# precharge.net
KiCad netlist of a schematic drawn in EAGLE
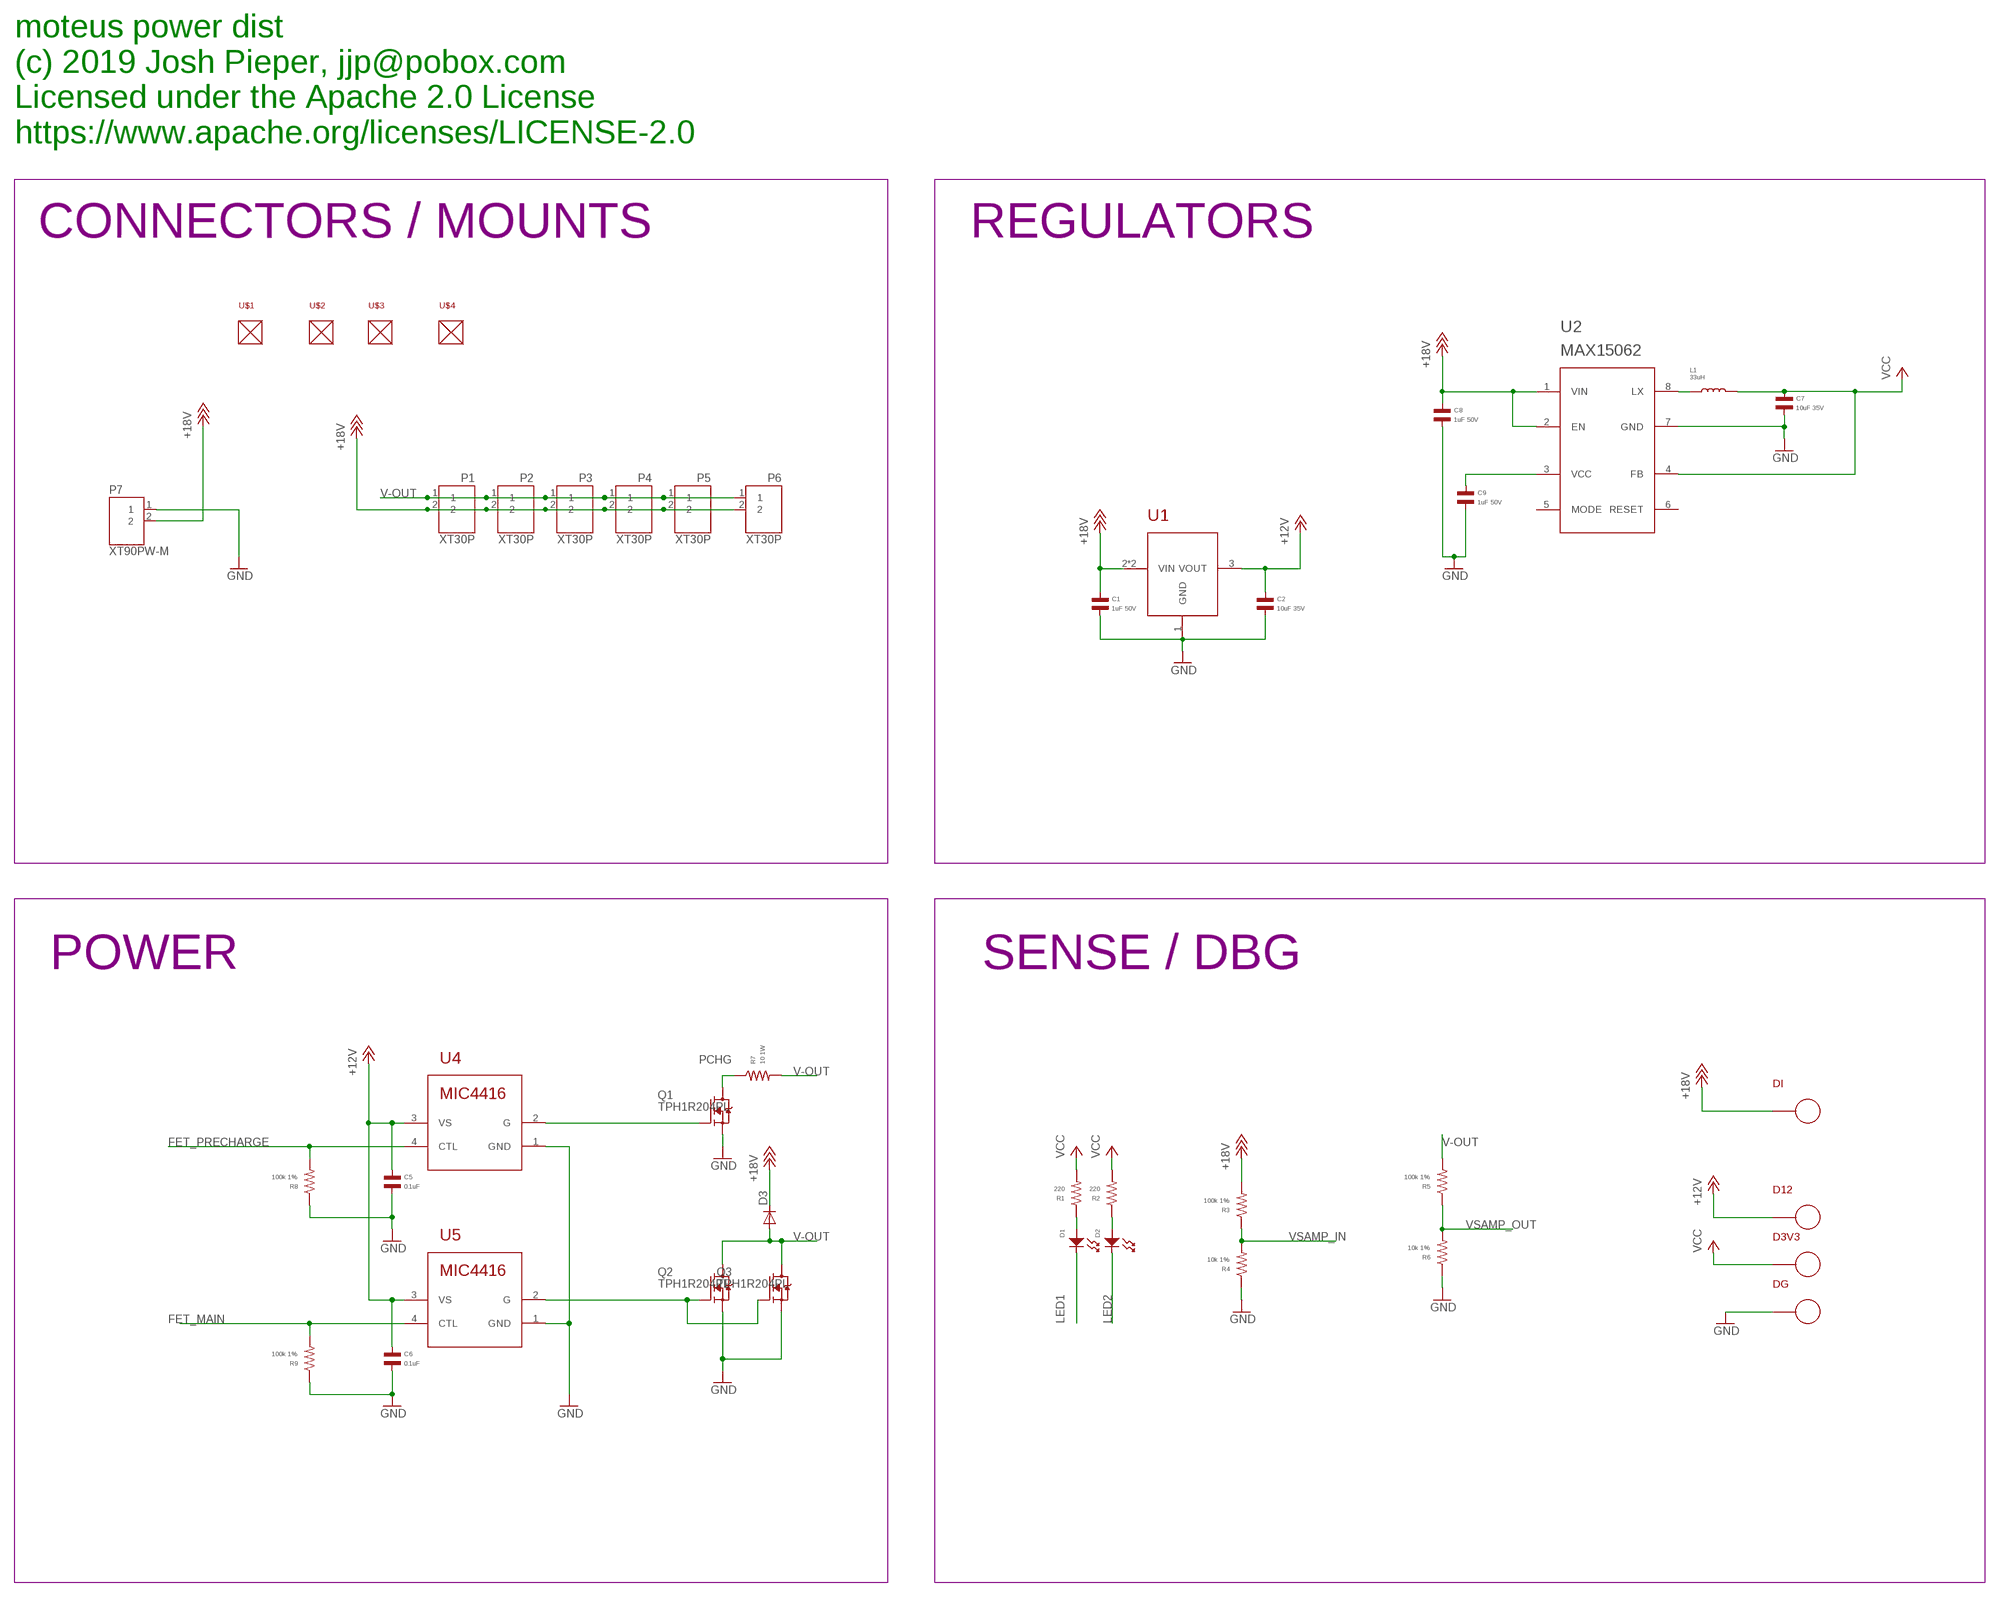
[diagram p0: schematic, sheet 1, part 1 of 2]
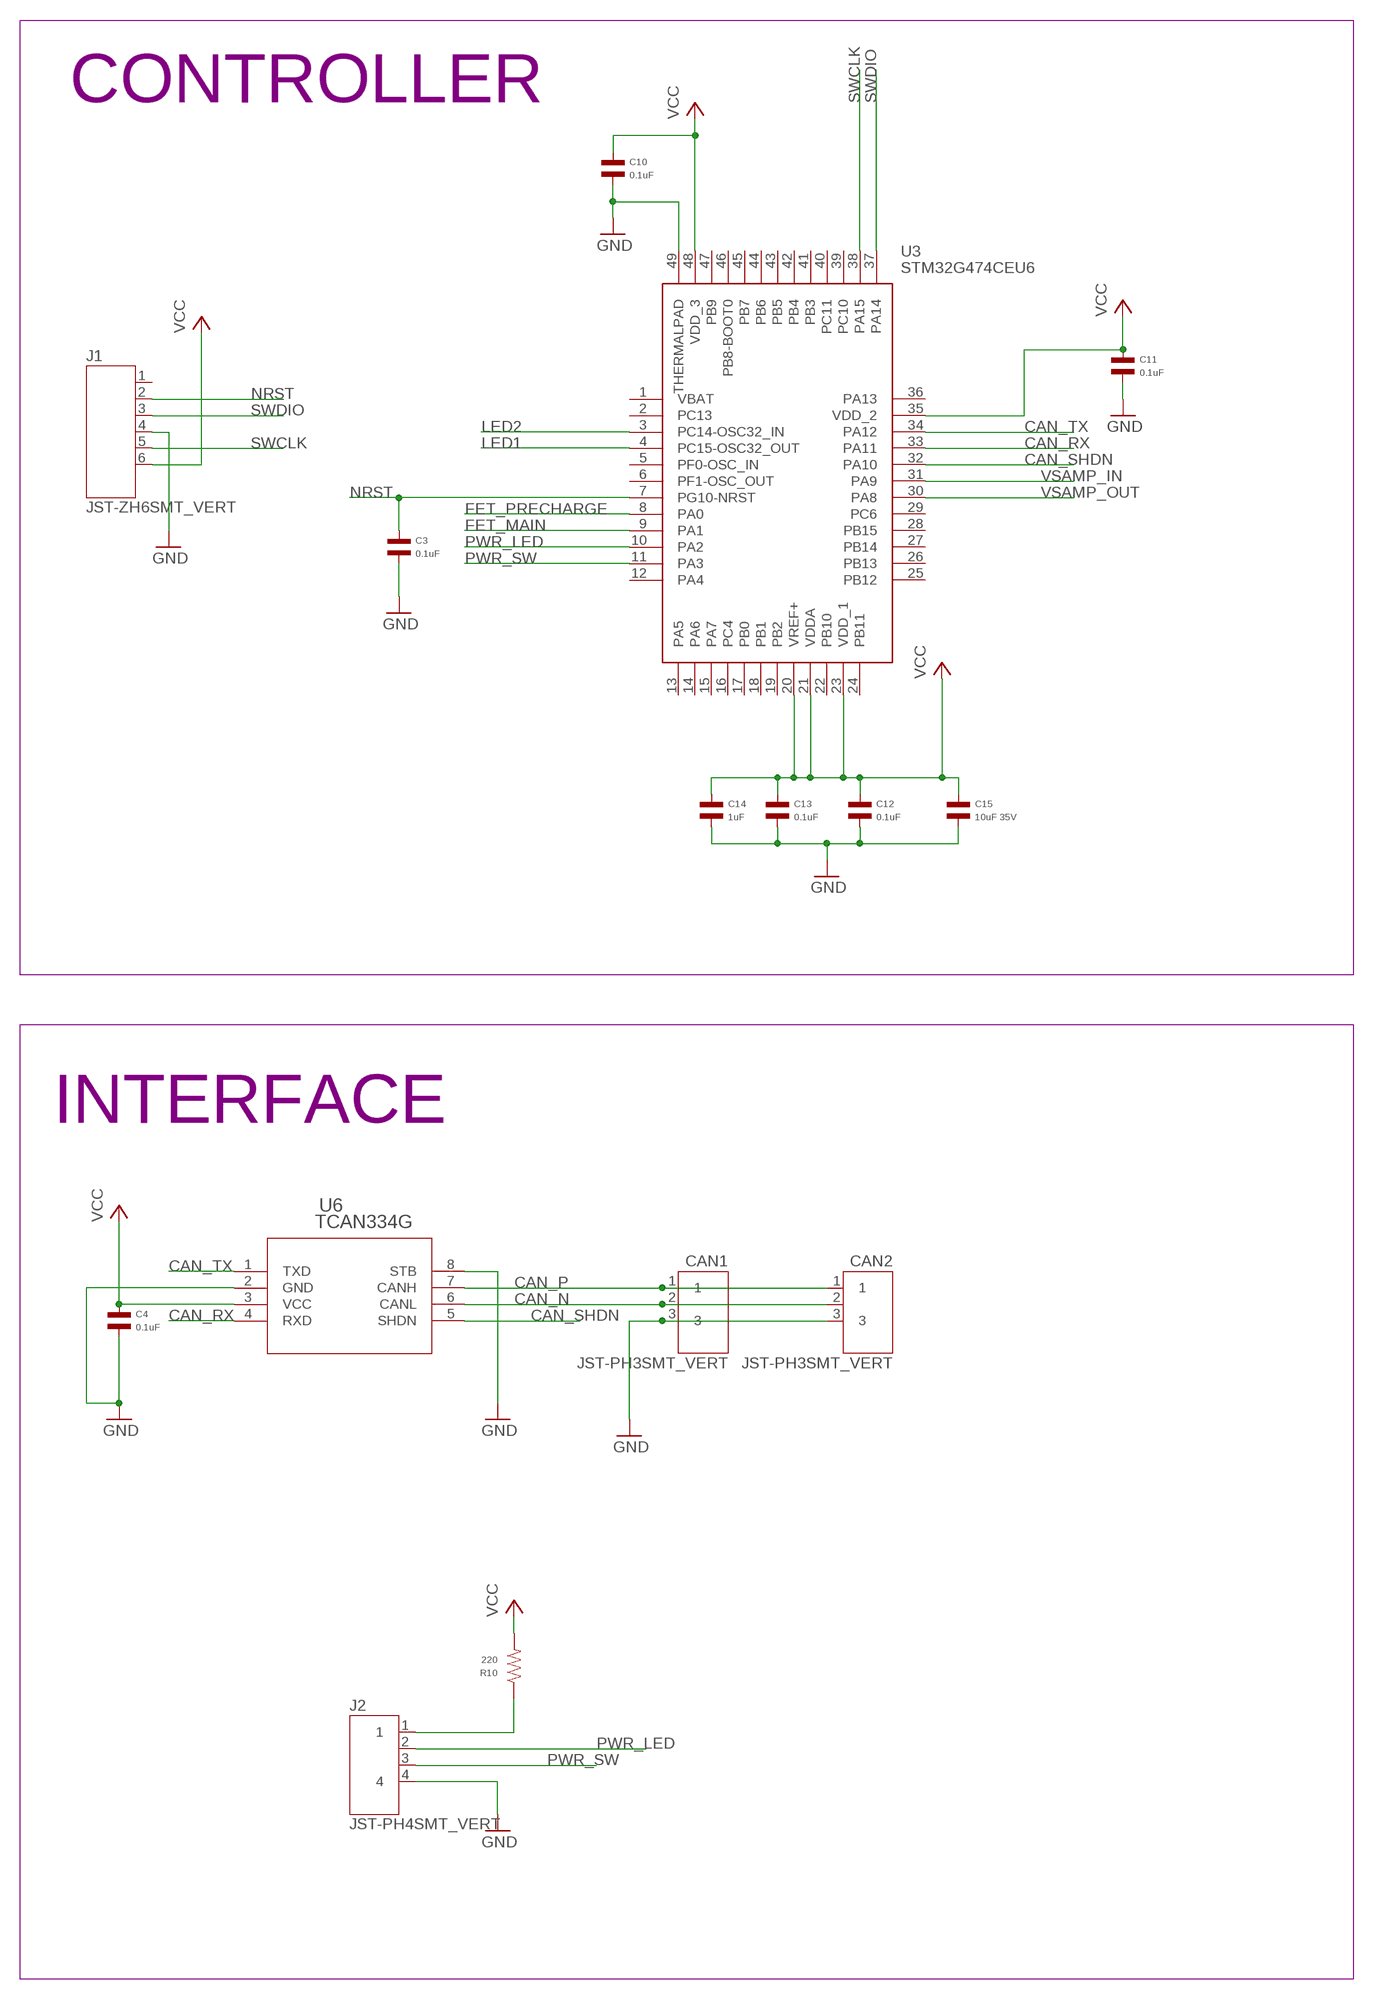
[diagram p1: schematic, sheet 1, part 2 of 2]

(export (version "E")
  (design (tool "Eeschema 10.0.6"))
  (components
    (comp (ref "C1")
      (value "1uF 50V")
      (footprint "eagle-import:C0603")
      (fields (field (name "MF") "SAMSUNG") (field (name "MPN") "CL10A105KB8NNNC"))
      (libsource (lib "eagle-import") (part "CAPACITOR_NP_0603"))
    )
    (comp (ref "C2")
      (value "10uF 35V")
      (footprint "eagle-import:C1206")
      (fields (field (name "MF") "TDK") (field (name "MPN") "CGA5L1X7R1V106K160AC"))
      (libsource (lib "eagle-import") (part "CAPACITOR_NP_1206"))
    )
    (comp (ref "C3")
      (value "0.1uF")
      (footprint "eagle-import:C0402")
      (fields (field (name "HOUSEPART") "1") (field (name "MPN") "MF-CAP-0402-0.1uF"))
      (libsource (lib "eagle-import") (part "CAPACITOR_NP_0402"))
    )
    (comp (ref "C4")
      (value "0.1uF")
      (footprint "eagle-import:C0402")
      (fields (field (name "HOUSEPART") "1") (field (name "MPN") "MF-CAP-0402-0.1uF"))
      (libsource (lib "eagle-import") (part "CAPACITOR_NP_0402"))
    )
    (comp (ref "C5")
      (value "0.1uF")
      (footprint "eagle-import:C0402")
      (fields (field (name "HOUSEPART") "1") (field (name "MPN") "MF-CAP-0402-0.1uF"))
      (libsource (lib "eagle-import") (part "CAPACITOR_NP_0402"))
    )
    (comp (ref "C6")
      (value "0.1uF")
      (footprint "eagle-import:C0402")
      (fields (field (name "HOUSEPART") "1") (field (name "MPN") "MF-CAP-0402-0.1uF"))
      (libsource (lib "eagle-import") (part "CAPACITOR_NP_0402"))
    )
    (comp (ref "C7")
      (value "10uF 35V")
      (footprint "eagle-import:C1206")
      (fields (field (name "MF") "TDK") (field (name "MPN") "CGA5L1X7R1V106K160AC"))
      (libsource (lib "eagle-import") (part "CAPACITOR_NP_1206"))
    )
    (comp (ref "C8")
      (value "1uF 50V")
      (footprint "eagle-import:C0603")
      (fields (field (name "MF") "SAMSUNG") (field (name "MPN") "CL10A105KB8NNNC"))
      (libsource (lib "eagle-import") (part "CAPACITOR_NP_0603"))
    )
    (comp (ref "C9")
      (value "1uF 50V")
      (footprint "eagle-import:C0603")
      (fields (field (name "MF") "SAMSUNG") (field (name "MPN") "CL10A105KB8NNNC"))
      (libsource (lib "eagle-import") (part "CAPACITOR_NP_0603"))
    )
    (comp (ref "C10")
      (value "0.1uF")
      (footprint "eagle-import:C0402")
      (fields (field (name "HOUSEPART") "1") (field (name "MPN") "MF-CAP-0402-0.1uF"))
      (libsource (lib "eagle-import") (part "CAPACITOR_NP_0402"))
    )
    (comp (ref "C11")
      (value "0.1uF")
      (footprint "eagle-import:C0402")
      (fields (field (name "HOUSEPART") "1") (field (name "MPN") "MF-CAP-0402-0.1uF"))
      (libsource (lib "eagle-import") (part "CAPACITOR_NP_0402"))
    )
    (comp (ref "C12")
      (value "0.1uF")
      (footprint "eagle-import:C0402")
      (fields (field (name "HOUSEPART") "1") (field (name "MPN") "MF-CAP-0402-0.1uF"))
      (libsource (lib "eagle-import") (part "CAPACITOR_NP_0402"))
    )
    (comp (ref "C13")
      (value "0.1uF")
      (footprint "eagle-import:C0402")
      (fields (field (name "HOUSEPART") "1") (field (name "MPN") "MF-CAP-0402-0.1uF"))
      (libsource (lib "eagle-import") (part "CAPACITOR_NP_0402"))
    )
    (comp (ref "C14")
      (value "1uF")
      (footprint "eagle-import:C0402")
      (fields (field (name "HOUSEPART") "1") (field (name "MPN") "MF-CAP-0402-1uF"))
      (libsource (lib "eagle-import") (part "CAPACITOR_NP_0402"))
    )
    (comp (ref "C15")
      (value "10uF 35V")
      (footprint "eagle-import:C1206")
      (fields (field (name "MF") "TDK") (field (name "MPN") "CGA5L1X7R1V106K160AC"))
      (libsource (lib "eagle-import") (part "CAPACITOR_NP_1206"))
    )
    (comp (ref "CAN1")
      (value "JST-PH3SMT_VERT")
      (footprint "eagle-import:JST_B3B_PH-SM4-TB(LF)(SN)")
      (fields (field (name "MF") "JST") (field (name "MPN") "B3B-PH-SM4-TB(LF)(SN)"))
      (libsource (lib "eagle-import") (part "JST-PH3SMT_VERT"))
    )
    (comp (ref "CAN2")
      (value "JST-PH3SMT_VERT")
      (footprint "eagle-import:JST_B3B_PH-SM4-TB(LF)(SN)")
      (fields (field (name "MF") "JST") (field (name "MPN") "B3B-PH-SM4-TB(LF)(SN)"))
      (libsource (lib "eagle-import") (part "JST-PH3SMT_VERT"))
    )
    (comp (ref "D1")
      (value "LED_SINGLE-0603")
      (footprint "eagle-import:LED0603")
      (fields
        (field (name "HOUSEPART") "NO")
        (field (name "HOUSEPART_1") "1")
        (field (name "MPN") "MF-LED-0603-RED")
      )
      (libsource (lib "eagle-import") (part "LED_SINGLE-0603"))
    )
    (comp (ref "D2")
      (value "LED_SINGLE-0603")
      (footprint "eagle-import:LED0603")
      (fields
        (field (name "HOUSEPART") "NO")
        (field (name "HOUSEPART_1") "1")
        (field (name "MPN") "MF-LED-0603-RED")
      )
      (libsource (lib "eagle-import") (part "LED_SINGLE-0603"))
    )
    (comp (ref "D3")
      (value "DIODE-")
      (footprint "eagle-import:DO-214AB")
      (fields (field (name "MF") "MICRO COMMERCIAL") (field (name "MPN") "SK510L-TP"))
      (libsource (lib "eagle-import") (part "DIODE-"))
    )
    (comp (ref "D3V3")
      (value "PAD24AWG_PAD")
      (footprint "eagle-import:24AWG_PAD")
      (libsource (lib "eagle-import") (part "PAD24AWG_PAD"))
    )
    (comp (ref "D12")
      (value "PAD24AWG_PAD")
      (footprint "eagle-import:24AWG_PAD")
      (libsource (lib "eagle-import") (part "PAD24AWG_PAD"))
    )
    (comp (ref "DG")
      (value "PAD24AWG_PAD")
      (footprint "eagle-import:24AWG_PAD")
      (libsource (lib "eagle-import") (part "PAD24AWG_PAD"))
    )
    (comp (ref "DI")
      (value "PAD24AWG_PAD")
      (footprint "eagle-import:24AWG_PAD")
      (libsource (lib "eagle-import") (part "PAD24AWG_PAD"))
    )
    (comp (ref "J1")
      (value "JST-ZH6SMT_VERT")
      (footprint "eagle-import:JST_B6B-ZR-SM4-TF(LF)(SN)")
      (fields (field (name "MF") "JST") (field (name "MPN") "B6B-ZR-SM4-TF(LF)(SN)"))
      (libsource (lib "eagle-import") (part "JST-ZH6SMT_VERT"))
    )
    (comp (ref "J2")
      (value "JST-PH4SMT_VERT")
      (footprint "eagle-import:JST_B4B_PH-SM4-TB(LF)(SN)")
      (fields (field (name "MF") "JST") (field (name "MPN") "B4B-PH-SM4-TB(LF)(SN)"))
      (libsource (lib "eagle-import") (part "JST-PH4SMT_VERT"))
    )
    (comp (ref "L1")
      (value "33uH")
      (footprint "eagle-import:L1210")
      (fields (field (name "MF") "TDK") (field (name "MPN") "NLFV32T-330K-EF") (field (name "POPULATE") "1"))
      (libsource (lib "eagle-import") (part "INDUCTOR_1210"))
    )
    (comp (ref "P1")
      (value "XT30P")
      (footprint "eagle-import:XT30P")
      (libsource (lib "eagle-import") (part "XT30P"))
    )
    (comp (ref "P2")
      (value "XT30P")
      (footprint "eagle-import:XT30P")
      (libsource (lib "eagle-import") (part "XT30P"))
    )
    (comp (ref "P3")
      (value "XT30P")
      (footprint "eagle-import:XT30P")
      (libsource (lib "eagle-import") (part "XT30P"))
    )
    (comp (ref "P4")
      (value "XT30P")
      (footprint "eagle-import:XT30P")
      (libsource (lib "eagle-import") (part "XT30P"))
    )
    (comp (ref "P5")
      (value "XT30P")
      (footprint "eagle-import:XT30P")
      (libsource (lib "eagle-import") (part "XT30P"))
    )
    (comp (ref "P6")
      (value "XT30P")
      (footprint "eagle-import:XT30P")
      (libsource (lib "eagle-import") (part "XT30P"))
    )
    (comp (ref "P7")
      (value "XT90PW-M")
      (footprint "eagle-import:XT90PW-M")
      (libsource (lib "eagle-import") (part "XT90PW-M"))
    )
    (comp (ref "Q1")
      (value "TPH1R204PL")
      (footprint "eagle-import:SOP_ADVANCE")
      (fields (field (name "MF") "Toshiba") (field (name "MPN") "TPH1R204PL,L1Q"))
      (libsource (lib "eagle-import") (part "TPH1R204PL"))
    )
    (comp (ref "Q2")
      (value "TPH1R204PL")
      (footprint "eagle-import:SOP_ADVANCE")
      (fields (field (name "MF") "Toshiba") (field (name "MPN") "TPH1R204PL,L1Q"))
      (libsource (lib "eagle-import") (part "TPH1R204PL"))
    )
    (comp (ref "Q3")
      (value "TPH1R204PL")
      (footprint "eagle-import:SOP_ADVANCE")
      (fields (field (name "MF") "Toshiba") (field (name "MPN") "TPH1R204PL,L1Q"))
      (libsource (lib "eagle-import") (part "TPH1R204PL"))
    )
    (comp (ref "R1")
      (value "220")
      (footprint "eagle-import:R0603")
      (fields (field (name "HOUSEPART") "1") (field (name "MPN") "MF-RES-0603-220"))
      (libsource (lib "eagle-import") (part "RESISTOR_0603"))
    )
    (comp (ref "R2")
      (value "220")
      (footprint "eagle-import:R0603")
      (fields (field (name "HOUSEPART") "1") (field (name "MPN") "MF-RES-0603-220"))
      (libsource (lib "eagle-import") (part "RESISTOR_0603"))
    )
    (comp (ref "R3")
      (value "100k 1%")
      (footprint "eagle-import:R0603")
      (fields (field (name "MF") "VISHAY") (field (name "MPN") "CRCW0603100KFKEA"))
      (libsource (lib "eagle-import") (part "RESISTOR_0603"))
    )
    (comp (ref "R4")
      (value "10k 1%")
      (footprint "eagle-import:R0603")
      (fields (field (name "MF") "PANASONIC") (field (name "MPN") "ERJ-3EKF1002V"))
      (libsource (lib "eagle-import") (part "RESISTOR_0603"))
    )
    (comp (ref "R5")
      (value "100k 1%")
      (footprint "eagle-import:R0603")
      (fields (field (name "MF") "VISHAY") (field (name "MPN") "CRCW0603100KFKEA"))
      (libsource (lib "eagle-import") (part "RESISTOR_0603"))
    )
    (comp (ref "R6")
      (value "10k 1%")
      (footprint "eagle-import:R0603")
      (fields (field (name "MF") "PANASONIC") (field (name "MPN") "ERJ-3EKF1002V"))
      (libsource (lib "eagle-import") (part "RESISTOR_0603"))
    )
    (comp (ref "R7")
      (value "10 1W")
      (footprint "eagle-import:R1206")
      (fields (field (name "MF") "Susumu") (field (name "MPN") "HRG3216Q-10R0-D-T1"))
      (libsource (lib "eagle-import") (part "RESISTOR_1206"))
    )
    (comp (ref "R8")
      (value "100k 1%")
      (footprint "eagle-import:R0603")
      (fields (field (name "MF") "VISHAY") (field (name "MPN") "CRCW0603100KFKEA"))
      (libsource (lib "eagle-import") (part "RESISTOR_0603"))
    )
    (comp (ref "R9")
      (value "100k 1%")
      (footprint "eagle-import:R0603")
      (fields (field (name "MF") "VISHAY") (field (name "MPN") "CRCW0603100KFKEA"))
      (libsource (lib "eagle-import") (part "RESISTOR_0603"))
    )
    (comp (ref "R10")
      (value "220")
      (footprint "eagle-import:R0603")
      (fields (field (name "HOUSEPART") "1") (field (name "MPN") "MF-RES-0603-220"))
      (libsource (lib "eagle-import") (part "RESISTOR_0603"))
    )
    (comp (ref "U$1")
      (value "MOUNT")
      (footprint "eagle-import:M2.5MOUNT")
      (libsource (lib "eagle-import") (part "MOUNT"))
    )
    (comp (ref "U$2")
      (value "MOUNT")
      (footprint "eagle-import:M2.5MOUNT")
      (libsource (lib "eagle-import") (part "MOUNT"))
    )
    (comp (ref "U$3")
      (value "MOUNT")
      (footprint "eagle-import:M2.5MOUNT")
      (libsource (lib "eagle-import") (part "MOUNT"))
    )
    (comp (ref "U$4")
      (value "MOUNT")
      (footprint "eagle-import:M2.5MOUNT")
      (libsource (lib "eagle-import") (part "MOUNT"))
    )
    (comp (ref "U1")
      (value "ZXTR2012Z")
      (footprint "eagle-import:SOT89")
      (fields (field (name "MF") "DIODES INC") (field (name "MPN") "ZXTR2012Z-13"))
      (libsource (lib "eagle-import") (part "ZXTR2012Z"))
    )
    (comp (ref "U2")
      (value "MAX150628TDFN")
      (footprint "eagle-import:8TDFN")
      (fields (field (name "MF") "MAXIM") (field (name "MPN") "MAX15062AATA+T"))
      (libsource (lib "eagle-import") (part "MAX150628TDFN"))
    )
    (comp (ref "U3")
      (value "STM32G474CEU6")
      (footprint "eagle-import:QFN50P700X700X60-49N")
      (fields (field (name "MOUSER_PART_NUMBER") "511-STM32G474CEU6") (field (name "MF") "ST"))
      (libsource (lib "eagle-import") (part "STM32G474CEU6"))
    )
    (comp (ref "U4")
      (value "MIC4416")
      (footprint "eagle-import:SOT143")
      (fields (field (name "MF") "MICROCHIP") (field (name "MPN") "MIC4416YM4-TR"))
      (libsource (lib "eagle-import") (part "MIC4416"))
    )
    (comp (ref "U5")
      (value "MIC4416")
      (footprint "eagle-import:SOT143")
      (fields (field (name "MF") "MICROCHIP") (field (name "MPN") "MIC4416YM4-TR"))
      (libsource (lib "eagle-import") (part "MIC4416"))
    )
    (comp (ref "U6")
      (value "TCAN334G")
      (footprint "eagle-import:SOIC8")
      (fields (field (name "MF") "TI") (field (name "MPN") "TCAN334GDR"))
      (libsource (lib "eagle-import") (part "TCAN334G"))
    )
  )
  (nets
    (net (code "1") (name "+12V") (class "Default")
      (node (ref "C2") (pin "P$1") (pinfunction "P$1_P$1") (pintype "passive"))
      (node (ref "C5") (pin "P$1") (pinfunction "P$1_P$1") (pintype "passive"))
      (node (ref "C6") (pin "P$1") (pinfunction "P$1_P$1") (pintype "passive"))
      (node (ref "D12") (pin "P$1") (pinfunction "P$1_P$1") (pintype "bidirectional"))
      (node (ref "U1") (pin "3") (pinfunction "VOUT_3") (pintype "bidirectional"))
      (node (ref "U4") (pin "3") (pinfunction "VS_3") (pintype "bidirectional"))
      (node (ref "U5") (pin "3") (pinfunction "VS_3") (pintype "bidirectional"))
    )
    (net (code "2") (name "+18V") (class "Default")
      (node (ref "C1") (pin "P$1") (pinfunction "P$1_P$1") (pintype "passive"))
      (node (ref "C8") (pin "P$1") (pinfunction "P$1_P$1") (pintype "passive"))
      (node (ref "D3") (pin "C") (pinfunction "C_C") (pintype "passive"))
      (node (ref "DI") (pin "P$1") (pinfunction "P$1_P$1") (pintype "bidirectional"))
      (node (ref "P1") (pin "2") (pinfunction "2_2") (pintype "passive"))
      (node (ref "P2") (pin "2") (pinfunction "2_2") (pintype "passive"))
      (node (ref "P3") (pin "2") (pinfunction "2_2") (pintype "passive"))
      (node (ref "P4") (pin "2") (pinfunction "2_2") (pintype "passive"))
      (node (ref "P5") (pin "2") (pinfunction "2_2") (pintype "passive"))
      (node (ref "P6") (pin "2") (pinfunction "2_2") (pintype "passive"))
      (node (ref "P7") (pin "2") (pinfunction "2_2") (pintype "passive"))
      (node (ref "R3") (pin "P$2") (pinfunction "P$2_P$2") (pintype "passive"))
      (node (ref "U1") (pin "2") (pinfunction "VIN_2") (pintype "bidirectional"))
      (node (ref "U1") (pin "PAD") (pinfunction "VIN_PAD") (pintype "bidirectional"))
      (node (ref "U2") (pin "1") (pinfunction "VIN_1") (pintype "passive"))
      (node (ref "U2") (pin "2") (pinfunction "EN_2") (pintype "passive"))
    )
    (net (code "3") (name "/CAN_N") (class "Default")
      (node (ref "CAN1") (pin "2") (pinfunction "2_2") (pintype "passive"))
      (node (ref "CAN2") (pin "2") (pinfunction "2_2") (pintype "passive"))
      (node (ref "U6") (pin "6") (pinfunction "CANL_6") (pintype "bidirectional"))
    )
    (net (code "4") (name "/CAN_P") (class "Default")
      (node (ref "CAN1") (pin "1") (pinfunction "1_1") (pintype "passive"))
      (node (ref "CAN2") (pin "1") (pinfunction "1_1") (pintype "passive"))
      (node (ref "U6") (pin "7") (pinfunction "CANH_7") (pintype "bidirectional"))
    )
    (net (code "5") (name "/CAN_RX") (class "Default")
      (node (ref "U3") (pin "33") (pinfunction "PA11_33") (pintype "bidirectional"))
      (node (ref "U6") (pin "4") (pinfunction "RXD_4") (pintype "output"))
    )
    (net (code "6") (name "/CAN_SHDN") (class "Default")
      (node (ref "U3") (pin "32") (pinfunction "PA10_32") (pintype "bidirectional"))
      (node (ref "U6") (pin "5") (pinfunction "SHDN_5") (pintype "input"))
    )
    (net (code "7") (name "/CAN_TX") (class "Default")
      (node (ref "U3") (pin "34") (pinfunction "PA12_34") (pintype "bidirectional"))
      (node (ref "U6") (pin "1") (pinfunction "TXD_1") (pintype "input"))
    )
    (net (code "8") (name "/FET_MAIN") (class "Default")
      (node (ref "R9") (pin "P$2") (pinfunction "P$2_P$2") (pintype "passive"))
      (node (ref "U3") (pin "9") (pinfunction "PA1_9") (pintype "bidirectional"))
      (node (ref "U5") (pin "4") (pinfunction "CTL_4") (pintype "bidirectional"))
    )
    (net (code "9") (name "/FET_PRECHARGE") (class "Default")
      (node (ref "R8") (pin "P$2") (pinfunction "P$2_P$2") (pintype "passive"))
      (node (ref "U3") (pin "8") (pinfunction "PA0_8") (pintype "bidirectional"))
      (node (ref "U4") (pin "4") (pinfunction "CTL_4") (pintype "bidirectional"))
    )
    (net (code "10") (name "/LED1") (class "Default")
      (node (ref "D1") (pin "CATHODE") (pinfunction "CATHODE_CATHODE") (pintype "power_in"))
      (node (ref "U3") (pin "4") (pinfunction "PC15-OSC32_OUT_4") (pintype "bidirectional"))
    )
    (net (code "11") (name "/LED2") (class "Default")
      (node (ref "D2") (pin "CATHODE") (pinfunction "CATHODE_CATHODE") (pintype "power_in"))
      (node (ref "U3") (pin "3") (pinfunction "PC14-OSC32_IN_3") (pintype "bidirectional"))
    )
    (net (code "12") (name "/NRST") (class "Default")
      (node (ref "C3") (pin "P$1") (pinfunction "P$1_P$1") (pintype "passive"))
      (node (ref "J1") (pin "2") (pinfunction "2_2") (pintype "passive"))
      (node (ref "U3") (pin "7") (pinfunction "PG10-NRST_7") (pintype "bidirectional"))
    )
    (net (code "13") (name "/PCHG") (class "Default")
      (node (ref "Q1") (pin "5") (pinfunction "D_5") (pintype "passive"))
      (node (ref "Q1") (pin "6") (pinfunction "D_6") (pintype "passive"))
      (node (ref "Q1") (pin "7") (pinfunction "D_7") (pintype "passive"))
      (node (ref "Q1") (pin "8") (pinfunction "D_8") (pintype "passive"))
      (node (ref "Q1") (pin "PAD") (pinfunction "D_PAD") (pintype "passive"))
      (node (ref "R7") (pin "P$1") (pinfunction "P$1_P$1") (pintype "passive"))
    )
    (net (code "14") (name "/PWR_LED") (class "Default")
      (node (ref "J2") (pin "2") (pinfunction "2_2") (pintype "passive"))
      (node (ref "U3") (pin "10") (pinfunction "PA2_10") (pintype "bidirectional"))
    )
    (net (code "15") (name "/PWR_SW") (class "Default")
      (node (ref "J2") (pin "3") (pinfunction "3_3") (pintype "passive"))
      (node (ref "U3") (pin "11") (pinfunction "PA3_11") (pintype "bidirectional"))
    )
    (net (code "16") (name "/SWCLK") (class "Default")
      (node (ref "J1") (pin "5") (pinfunction "5_5") (pintype "passive"))
      (node (ref "U3") (pin "38") (pinfunction "PA15_38") (pintype "bidirectional"))
    )
    (net (code "17") (name "/SWDIO") (class "Default")
      (node (ref "J1") (pin "3") (pinfunction "3_3") (pintype "passive"))
      (node (ref "U3") (pin "37") (pinfunction "PA14_37") (pintype "bidirectional"))
    )
    (net (code "18") (name "/V-OUT") (class "Default")
      (node (ref "D3") (pin "A") (pinfunction "A_A") (pintype "passive"))
      (node (ref "P1") (pin "1") (pinfunction "1_1") (pintype "passive"))
      (node (ref "P2") (pin "1") (pinfunction "1_1") (pintype "passive"))
      (node (ref "P3") (pin "1") (pinfunction "1_1") (pintype "passive"))
      (node (ref "P4") (pin "1") (pinfunction "1_1") (pintype "passive"))
      (node (ref "P5") (pin "1") (pinfunction "1_1") (pintype "passive"))
      (node (ref "P6") (pin "1") (pinfunction "1_1") (pintype "passive"))
      (node (ref "Q2") (pin "5") (pinfunction "D_5") (pintype "passive"))
      (node (ref "Q2") (pin "6") (pinfunction "D_6") (pintype "passive"))
      (node (ref "Q2") (pin "7") (pinfunction "D_7") (pintype "passive"))
      (node (ref "Q2") (pin "8") (pinfunction "D_8") (pintype "passive"))
      (node (ref "Q2") (pin "PAD") (pinfunction "D_PAD") (pintype "passive"))
      (node (ref "Q3") (pin "5") (pinfunction "D_5") (pintype "passive"))
      (node (ref "Q3") (pin "6") (pinfunction "D_6") (pintype "passive"))
      (node (ref "Q3") (pin "7") (pinfunction "D_7") (pintype "passive"))
      (node (ref "Q3") (pin "8") (pinfunction "D_8") (pintype "passive"))
      (node (ref "Q3") (pin "PAD") (pinfunction "D_PAD") (pintype "passive"))
      (node (ref "R5") (pin "P$2") (pinfunction "P$2_P$2") (pintype "passive"))
      (node (ref "R7") (pin "P$2") (pinfunction "P$2_P$2") (pintype "passive"))
    )
    (net (code "19") (name "/VSAMP_IN") (class "Default")
      (node (ref "R3") (pin "P$1") (pinfunction "P$1_P$1") (pintype "passive"))
      (node (ref "R4") (pin "P$2") (pinfunction "P$2_P$2") (pintype "passive"))
      (node (ref "U3") (pin "31") (pinfunction "PA9_31") (pintype "bidirectional"))
    )
    (net (code "20") (name "/VSAMP_OUT") (class "Default")
      (node (ref "R5") (pin "P$1") (pinfunction "P$1_P$1") (pintype "passive"))
      (node (ref "R6") (pin "P$2") (pinfunction "P$2_P$2") (pintype "passive"))
      (node (ref "U3") (pin "30") (pinfunction "PA8_30") (pintype "bidirectional"))
    )
    (net (code "21") (name "GND") (class "Default")
      (node (ref "C1") (pin "P$2") (pinfunction "P$2_P$2") (pintype "passive"))
      (node (ref "C10") (pin "P$2") (pinfunction "P$2_P$2") (pintype "passive"))
      (node (ref "C11") (pin "P$2") (pinfunction "P$2_P$2") (pintype "passive"))
      (node (ref "C12") (pin "P$2") (pinfunction "P$2_P$2") (pintype "passive"))
      (node (ref "C13") (pin "P$2") (pinfunction "P$2_P$2") (pintype "passive"))
      (node (ref "C14") (pin "P$2") (pinfunction "P$2_P$2") (pintype "passive"))
      (node (ref "C15") (pin "P$2") (pinfunction "P$2_P$2") (pintype "passive"))
      (node (ref "C2") (pin "P$2") (pinfunction "P$2_P$2") (pintype "passive"))
      (node (ref "C3") (pin "P$2") (pinfunction "P$2_P$2") (pintype "passive"))
      (node (ref "C4") (pin "P$2") (pinfunction "P$2_P$2") (pintype "passive"))
      (node (ref "C5") (pin "P$2") (pinfunction "P$2_P$2") (pintype "passive"))
      (node (ref "C6") (pin "P$2") (pinfunction "P$2_P$2") (pintype "passive"))
      (node (ref "C7") (pin "P$2") (pinfunction "P$2_P$2") (pintype "passive"))
      (node (ref "C8") (pin "P$2") (pinfunction "P$2_P$2") (pintype "passive"))
      (node (ref "C9") (pin "P$2") (pinfunction "P$2_P$2") (pintype "passive"))
      (node (ref "CAN1") (pin "3") (pinfunction "3_3") (pintype "passive"))
      (node (ref "CAN2") (pin "3") (pinfunction "3_3") (pintype "passive"))
      (node (ref "DG") (pin "P$1") (pinfunction "P$1_P$1") (pintype "bidirectional"))
      (node (ref "J1") (pin "4") (pinfunction "4_4") (pintype "passive"))
      (node (ref "J2") (pin "4") (pinfunction "4_4") (pintype "passive"))
      (node (ref "P7") (pin "1") (pinfunction "1_1") (pintype "passive"))
      (node (ref "Q1") (pin "1") (pinfunction "S_1") (pintype "passive"))
      (node (ref "Q1") (pin "2") (pinfunction "S_2") (pintype "passive"))
      (node (ref "Q1") (pin "3") (pinfunction "S_3") (pintype "passive"))
      (node (ref "Q2") (pin "1") (pinfunction "S_1") (pintype "passive"))
      (node (ref "Q2") (pin "2") (pinfunction "S_2") (pintype "passive"))
      (node (ref "Q2") (pin "3") (pinfunction "S_3") (pintype "passive"))
      (node (ref "Q3") (pin "1") (pinfunction "S_1") (pintype "passive"))
      (node (ref "Q3") (pin "2") (pinfunction "S_2") (pintype "passive"))
      (node (ref "Q3") (pin "3") (pinfunction "S_3") (pintype "passive"))
      (node (ref "R4") (pin "P$1") (pinfunction "P$1_P$1") (pintype "passive"))
      (node (ref "R6") (pin "P$1") (pinfunction "P$1_P$1") (pintype "passive"))
      (node (ref "R8") (pin "P$1") (pinfunction "P$1_P$1") (pintype "passive"))
      (node (ref "R9") (pin "P$1") (pinfunction "P$1_P$1") (pintype "passive"))
      (node (ref "U1") (pin "1") (pinfunction "GND_1") (pintype "bidirectional"))
      (node (ref "U2") (pin "7") (pinfunction "GND_7") (pintype "passive"))
      (node (ref "U3") (pin "49") (pinfunction "THERMALPAD_49") (pintype "bidirectional"))
      (node (ref "U4") (pin "1") (pinfunction "GND_1") (pintype "bidirectional"))
      (node (ref "U5") (pin "1") (pinfunction "GND_1") (pintype "bidirectional"))
      (node (ref "U6") (pin "2") (pinfunction "GND_2") (pintype "power_in"))
      (node (ref "U6") (pin "8") (pinfunction "STB_8") (pintype "input"))
    )
    (net (code "22") (name "Net-(D1-PadANODE)") (class "Default")
      (node (ref "D1") (pin "ANODE") (pinfunction "ANODE_ANODE") (pintype "power_in"))
      (node (ref "R1") (pin "P$1") (pinfunction "P$1_P$1") (pintype "passive"))
    )
    (net (code "23") (name "Net-(D2-PadANODE)") (class "Default")
      (node (ref "D2") (pin "ANODE") (pinfunction "ANODE_ANODE") (pintype "power_in"))
      (node (ref "R2") (pin "P$1") (pinfunction "P$1_P$1") (pintype "passive"))
    )
    (net (code "24") (name "Net-(J2-Pad1)") (class "Default")
      (node (ref "J2") (pin "1") (pinfunction "1_1") (pintype "passive"))
      (node (ref "R10") (pin "P$1") (pinfunction "P$1_P$1") (pintype "passive"))
    )
    (net (code "25") (name "Net-(Q1-G)") (class "Default")
      (node (ref "Q1") (pin "4") (pinfunction "G_4") (pintype "passive"))
      (node (ref "U4") (pin "2") (pinfunction "G_2") (pintype "bidirectional"))
    )
    (net (code "26") (name "Net-(Q2-G)") (class "Default")
      (node (ref "Q2") (pin "4") (pinfunction "G_4") (pintype "passive"))
      (node (ref "Q3") (pin "4") (pinfunction "G_4") (pintype "passive"))
      (node (ref "U5") (pin "2") (pinfunction "G_2") (pintype "bidirectional"))
    )
    (net (code "27") (name "Net-(U2-LX)") (class "Default")
      (node (ref "L1") (pin "P$1") (pinfunction "P$1_P$1") (pintype "passive"))
      (node (ref "U2") (pin "8") (pinfunction "LX_8") (pintype "passive"))
    )
    (net (code "28") (name "Net-(U2-VCC)") (class "Default")
      (node (ref "C9") (pin "P$1") (pinfunction "P$1_P$1") (pintype "passive"))
      (node (ref "U2") (pin "3") (pinfunction "VCC_3") (pintype "passive"))
    )
    (net (code "29") (name "VCC") (class "Default")
      (node (ref "C10") (pin "P$1") (pinfunction "P$1_P$1") (pintype "passive"))
      (node (ref "C11") (pin "P$1") (pinfunction "P$1_P$1") (pintype "passive"))
      (node (ref "C12") (pin "P$1") (pinfunction "P$1_P$1") (pintype "passive"))
      (node (ref "C13") (pin "P$1") (pinfunction "P$1_P$1") (pintype "passive"))
      (node (ref "C14") (pin "P$1") (pinfunction "P$1_P$1") (pintype "passive"))
      (node (ref "C15") (pin "P$1") (pinfunction "P$1_P$1") (pintype "passive"))
      (node (ref "C4") (pin "P$1") (pinfunction "P$1_P$1") (pintype "passive"))
      (node (ref "C7") (pin "P$1") (pinfunction "P$1_P$1") (pintype "passive"))
      (node (ref "D3V3") (pin "P$1") (pinfunction "P$1_P$1") (pintype "bidirectional"))
      (node (ref "J1") (pin "6") (pinfunction "6_6") (pintype "passive"))
      (node (ref "L1") (pin "P$2") (pinfunction "P$2_P$2") (pintype "passive"))
      (node (ref "R1") (pin "P$2") (pinfunction "P$2_P$2") (pintype "passive"))
      (node (ref "R10") (pin "P$2") (pinfunction "P$2_P$2") (pintype "passive"))
      (node (ref "R2") (pin "P$2") (pinfunction "P$2_P$2") (pintype "passive"))
      (node (ref "U2") (pin "4") (pinfunction "FB_4") (pintype "passive"))
      (node (ref "U3") (pin "20") (pinfunction "VREF+_20") (pintype "bidirectional"))
      (node (ref "U3") (pin "21") (pinfunction "VDDA_21") (pintype "bidirectional"))
      (node (ref "U3") (pin "23") (pinfunction "VDD_1_23") (pintype "bidirectional"))
      (node (ref "U3") (pin "35") (pinfunction "VDD_2_35") (pintype "bidirectional"))
      (node (ref "U3") (pin "48") (pinfunction "VDD_3_48") (pintype "bidirectional"))
      (node (ref "U6") (pin "3") (pinfunction "VCC_3") (pintype "power_in"))
    )
    (net (code "30") (name "unconnected-(J1-Pad1)") (class "Default")
      (node (ref "J1") (pin "1") (pinfunction "1_1") (pintype "passive"))
    )
    (net (code "31") (name "unconnected-(U2-MODE-Pad5)") (class "Default")
      (node (ref "U2") (pin "5") (pinfunction "MODE_5") (pintype "passive"))
    )
    (net (code "32") (name "unconnected-(U2-RESET-Pad6)") (class "Default")
      (node (ref "U2") (pin "6") (pinfunction "RESET_6") (pintype "passive"))
    )
    (net (code "33") (name "unconnected-(U3-PA4-Pad12)") (class "Default")
      (node (ref "U3") (pin "12") (pinfunction "PA4_12") (pintype "bidirectional"))
    )
    (net (code "34") (name "unconnected-(U3-PA5-Pad13)") (class "Default")
      (node (ref "U3") (pin "13") (pinfunction "PA5_13") (pintype "bidirectional"))
    )
    (net (code "35") (name "unconnected-(U3-PA6-Pad14)") (class "Default")
      (node (ref "U3") (pin "14") (pinfunction "PA6_14") (pintype "bidirectional"))
    )
    (net (code "36") (name "unconnected-(U3-PA7-Pad15)") (class "Default")
      (node (ref "U3") (pin "15") (pinfunction "PA7_15") (pintype "bidirectional"))
    )
    (net (code "37") (name "unconnected-(U3-PA13-Pad36)") (class "Default")
      (node (ref "U3") (pin "36") (pinfunction "PA13_36") (pintype "bidirectional"))
    )
    (net (code "38") (name "unconnected-(U3-PB0-Pad17)") (class "Default")
      (node (ref "U3") (pin "17") (pinfunction "PB0_17") (pintype "bidirectional"))
    )
    (net (code "39") (name "unconnected-(U3-PB1-Pad18)") (class "Default")
      (node (ref "U3") (pin "18") (pinfunction "PB1_18") (pintype "bidirectional"))
    )
    (net (code "40") (name "unconnected-(U3-PB2-Pad19)") (class "Default")
      (node (ref "U3") (pin "19") (pinfunction "PB2_19") (pintype "bidirectional"))
    )
    (net (code "41") (name "unconnected-(U3-PB3-Pad41)") (class "Default")
      (node (ref "U3") (pin "41") (pinfunction "PB3_41") (pintype "bidirectional"))
    )
    (net (code "42") (name "unconnected-(U3-PB4-Pad42)") (class "Default")
      (node (ref "U3") (pin "42") (pinfunction "PB4_42") (pintype "bidirectional"))
    )
    (net (code "43") (name "unconnected-(U3-PB5-Pad43)") (class "Default")
      (node (ref "U3") (pin "43") (pinfunction "PB5_43") (pintype "bidirectional"))
    )
    (net (code "44") (name "unconnected-(U3-PB6-Pad44)") (class "Default")
      (node (ref "U3") (pin "44") (pinfunction "PB6_44") (pintype "bidirectional"))
    )
    (net (code "45") (name "unconnected-(U3-PB7-Pad45)") (class "Default")
      (node (ref "U3") (pin "45") (pinfunction "PB7_45") (pintype "bidirectional"))
    )
    (net (code "46") (name "unconnected-(U3-PB8-BOOT0-Pad46)") (class "Default")
      (node (ref "U3") (pin "46") (pinfunction "PB8-BOOT0_46") (pintype "bidirectional"))
    )
    (net (code "47") (name "unconnected-(U3-PB9-Pad47)") (class "Default")
      (node (ref "U3") (pin "47") (pinfunction "PB9_47") (pintype "bidirectional"))
    )
    (net (code "48") (name "unconnected-(U3-PB10-Pad22)") (class "Default")
      (node (ref "U3") (pin "22") (pinfunction "PB10_22") (pintype "bidirectional"))
    )
    (net (code "49") (name "unconnected-(U3-PB11-Pad24)") (class "Default")
      (node (ref "U3") (pin "24") (pinfunction "PB11_24") (pintype "bidirectional"))
    )
    (net (code "50") (name "unconnected-(U3-PB12-Pad25)") (class "Default")
      (node (ref "U3") (pin "25") (pinfunction "PB12_25") (pintype "bidirectional"))
    )
    (net (code "51") (name "unconnected-(U3-PB13-Pad26)") (class "Default")
      (node (ref "U3") (pin "26") (pinfunction "PB13_26") (pintype "bidirectional"))
    )
    (net (code "52") (name "unconnected-(U3-PB14-Pad27)") (class "Default")
      (node (ref "U3") (pin "27") (pinfunction "PB14_27") (pintype "bidirectional"))
    )
    (net (code "53") (name "unconnected-(U3-PB15-Pad28)") (class "Default")
      (node (ref "U3") (pin "28") (pinfunction "PB15_28") (pintype "bidirectional"))
    )
    (net (code "54") (name "unconnected-(U3-PC4-Pad16)") (class "Default")
      (node (ref "U3") (pin "16") (pinfunction "PC4_16") (pintype "bidirectional"))
    )
    (net (code "55") (name "unconnected-(U3-PC6-Pad29)") (class "Default")
      (node (ref "U3") (pin "29") (pinfunction "PC6_29") (pintype "bidirectional"))
    )
    (net (code "56") (name "unconnected-(U3-PC10-Pad39)") (class "Default")
      (node (ref "U3") (pin "39") (pinfunction "PC10_39") (pintype "bidirectional"))
    )
    (net (code "57") (name "unconnected-(U3-PC11-Pad40)") (class "Default")
      (node (ref "U3") (pin "40") (pinfunction "PC11_40") (pintype "bidirectional"))
    )
    (net (code "58") (name "unconnected-(U3-PC13-Pad2)") (class "Default")
      (node (ref "U3") (pin "2") (pinfunction "PC13_2") (pintype "bidirectional"))
    )
    (net (code "59") (name "unconnected-(U3-PF0-OSC_IN-Pad5)") (class "Default")
      (node (ref "U3") (pin "5") (pinfunction "PF0-OSC_IN_5") (pintype "bidirectional"))
    )
    (net (code "60") (name "unconnected-(U3-PF1-OSC_OUT-Pad6)") (class "Default")
      (node (ref "U3") (pin "6") (pinfunction "PF1-OSC_OUT_6") (pintype "bidirectional"))
    )
    (net (code "61") (name "unconnected-(U3-VBAT-Pad1)") (class "Default")
      (node (ref "U3") (pin "1") (pinfunction "VBAT_1") (pintype "bidirectional"))
    )
  )
)
